# voice_board_kombi_w_gp.net
KiCad netlist of a schematic drawn in EAGLE
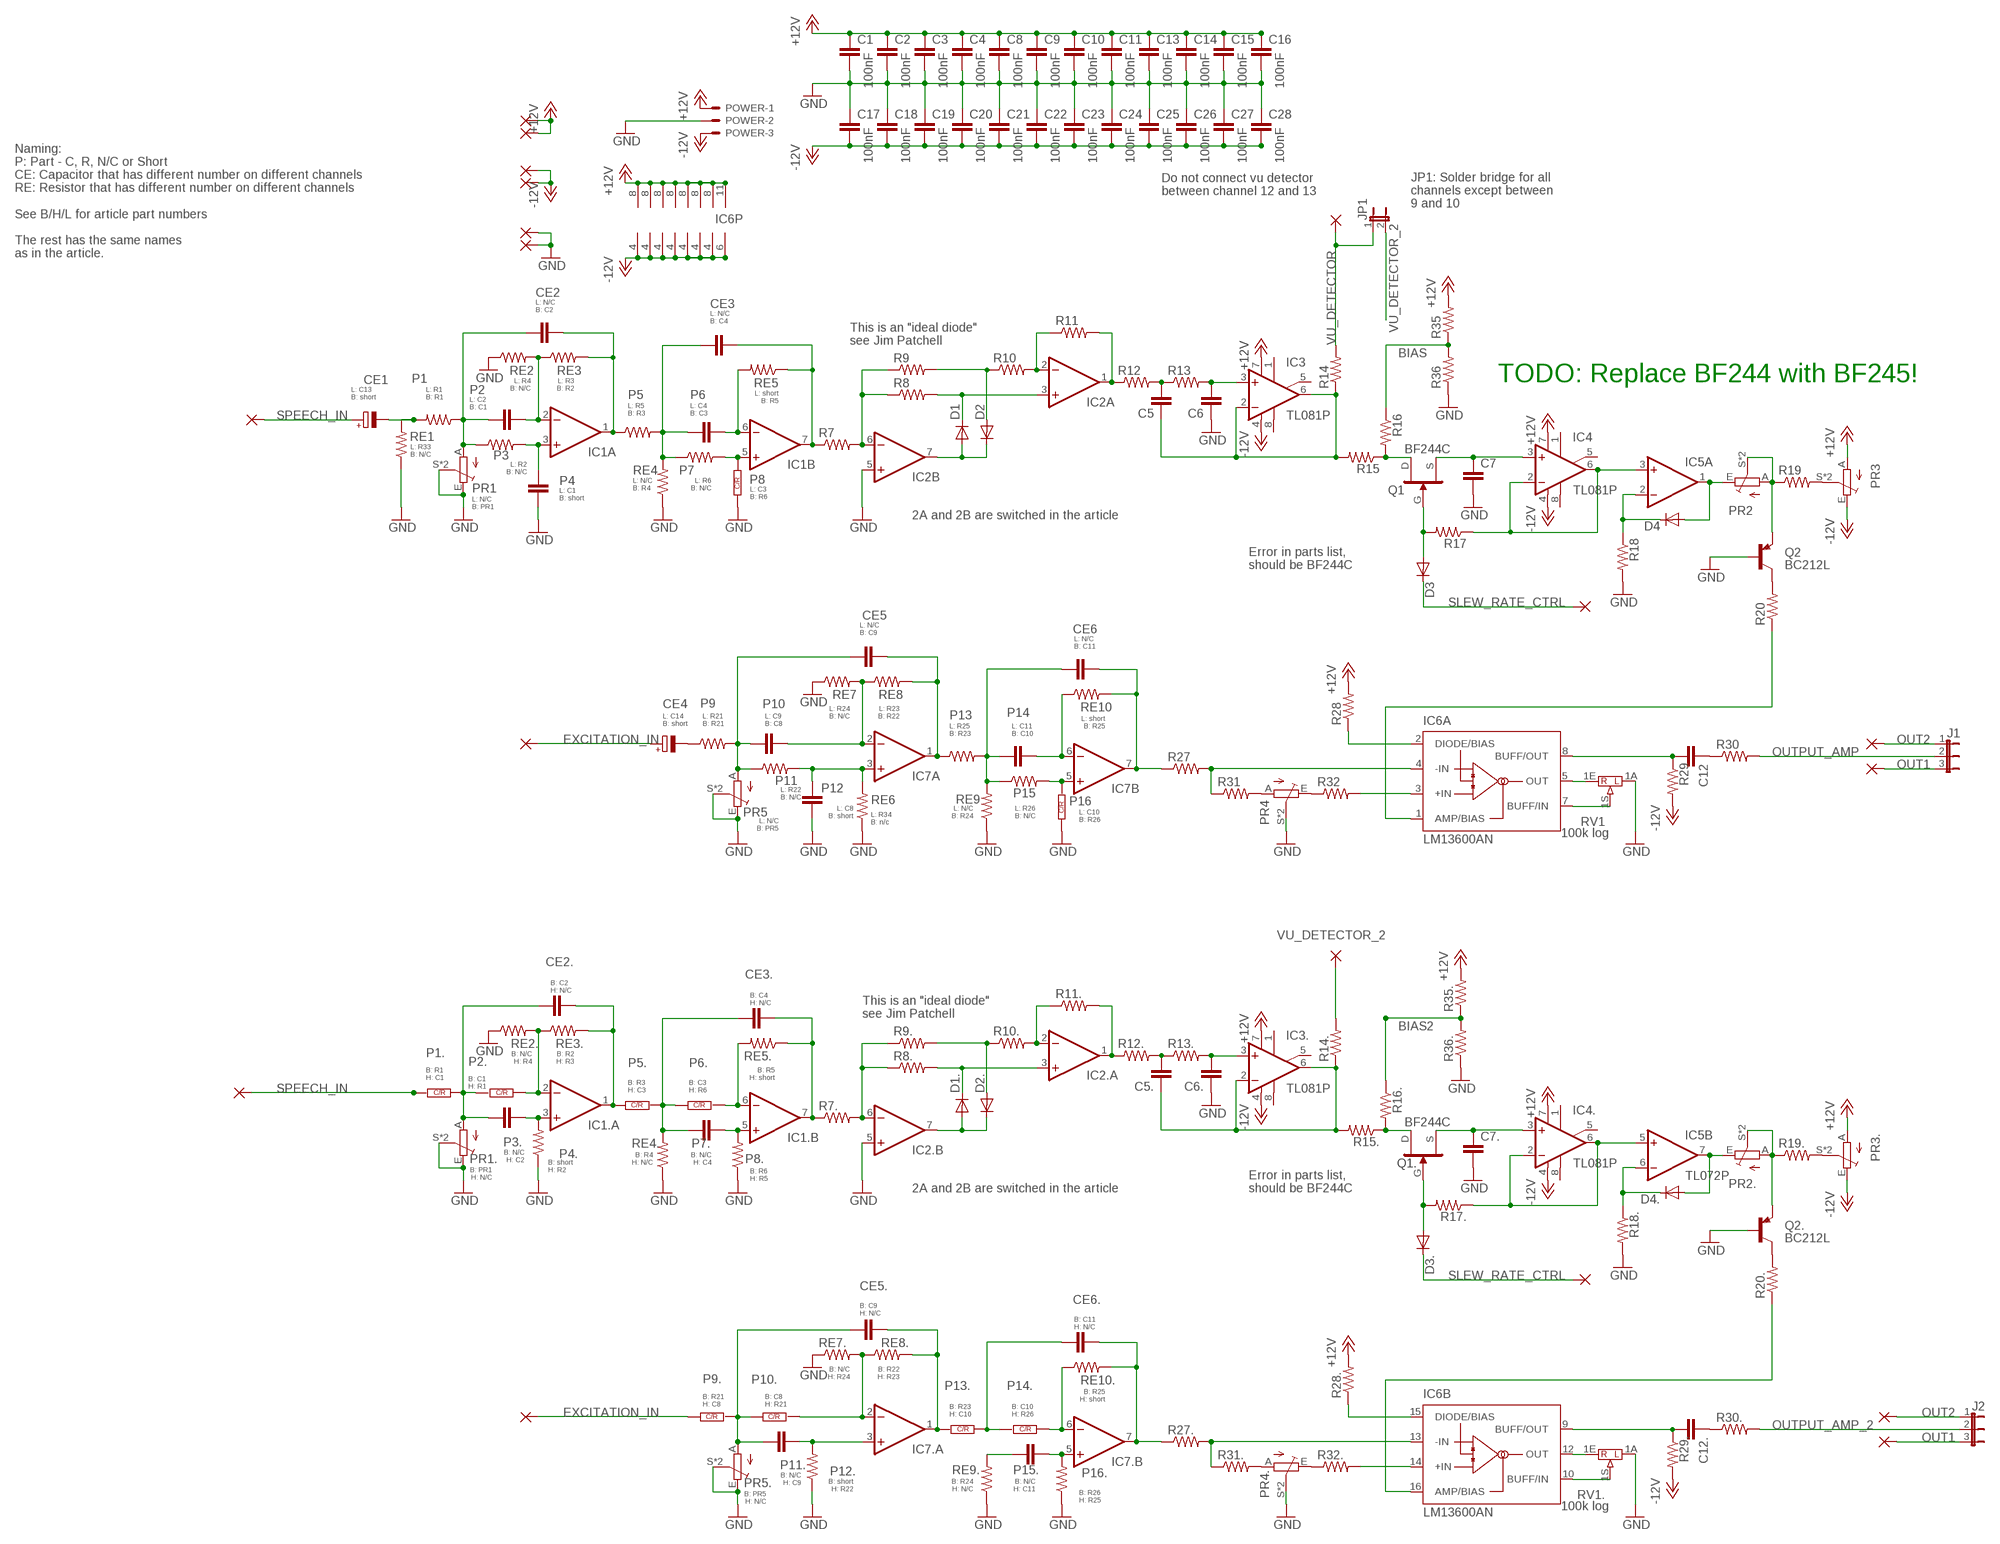
[diagram p0: schematic, sheet 1]

(export (version "E")
  (design (tool "Eeschema 10.0.6"))
  (components
    (comp (ref "C1")
      (value "100nF")
      (footprint "eagle-import:C0603")
      (libsource (lib "eagle-import") (part "C-EUC0603"))
    )
    (comp (ref "C2")
      (value "100nF")
      (footprint "eagle-import:C0603")
      (libsource (lib "eagle-import") (part "C-EUC0603"))
    )
    (comp (ref "C3")
      (value "100nF")
      (footprint "eagle-import:C0603")
      (libsource (lib "eagle-import") (part "C-EUC0603"))
    )
    (comp (ref "C4")
      (value "100nF")
      (footprint "eagle-import:C0603")
      (libsource (lib "eagle-import") (part "C-EUC0603"))
    )
    (comp (ref "C5")
      (value "C-EU050-035X075")
      (footprint "eagle-import:C050-035X075")
      (libsource (lib "eagle-import") (part "C-EU050-035X075"))
    )
    (comp (ref "C5.")
      (value "C-EU050-035X075")
      (footprint "eagle-import:C050-035X075")
      (libsource (lib "eagle-import") (part "C-EU050-035X075"))
    )
    (comp (ref "C6")
      (value "C-EU050-035X075")
      (footprint "eagle-import:C050-035X075")
      (libsource (lib "eagle-import") (part "C-EU050-035X075"))
    )
    (comp (ref "C6.")
      (value "C-EU050-035X075")
      (footprint "eagle-import:C050-035X075")
      (libsource (lib "eagle-import") (part "C-EU050-035X075"))
    )
    (comp (ref "C7")
      (value "C-EU050-035X075")
      (footprint "eagle-import:C050-035X075")
      (libsource (lib "eagle-import") (part "C-EU050-035X075"))
    )
    (comp (ref "C7.")
      (value "C-EU050-035X075")
      (footprint "eagle-import:C050-035X075")
      (libsource (lib "eagle-import") (part "C-EU050-035X075"))
    )
    (comp (ref "C8")
      (value "100nF")
      (footprint "eagle-import:C0603")
      (libsource (lib "eagle-import") (part "C-EUC0603"))
    )
    (comp (ref "C9")
      (value "100nF")
      (footprint "eagle-import:C0603")
      (libsource (lib "eagle-import") (part "C-EUC0603"))
    )
    (comp (ref "C10")
      (value "100nF")
      (footprint "eagle-import:C0603")
      (libsource (lib "eagle-import") (part "C-EUC0603"))
    )
    (comp (ref "C11")
      (value "100nF")
      (footprint "eagle-import:C0603")
      (libsource (lib "eagle-import") (part "C-EUC0603"))
    )
    (comp (ref "C12")
      (value "C-EU050-035X075")
      (footprint "eagle-import:C050-035X075")
      (libsource (lib "eagle-import") (part "C-EU050-035X075"))
    )
    (comp (ref "C12.")
      (value "C-EU050-035X075")
      (footprint "eagle-import:C050-035X075")
      (libsource (lib "eagle-import") (part "C-EU050-035X075"))
    )
    (comp (ref "C13")
      (value "100nF")
      (footprint "eagle-import:C0603")
      (libsource (lib "eagle-import") (part "C-EUC0603"))
    )
    (comp (ref "C14")
      (value "100nF")
      (footprint "eagle-import:C0603")
      (libsource (lib "eagle-import") (part "C-EUC0603"))
    )
    (comp (ref "C15")
      (value "100nF")
      (footprint "eagle-import:C0603")
      (libsource (lib "eagle-import") (part "C-EUC0603"))
    )
    (comp (ref "C16")
      (value "100nF")
      (footprint "eagle-import:C0603")
      (libsource (lib "eagle-import") (part "C-EUC0603"))
    )
    (comp (ref "C17")
      (value "100nF")
      (footprint "eagle-import:C0603")
      (libsource (lib "eagle-import") (part "C-EUC0603"))
    )
    (comp (ref "C18")
      (value "100nF")
      (footprint "eagle-import:C0603")
      (libsource (lib "eagle-import") (part "C-EUC0603"))
    )
    (comp (ref "C19")
      (value "100nF")
      (footprint "eagle-import:C0603")
      (libsource (lib "eagle-import") (part "C-EUC0603"))
    )
    (comp (ref "C20")
      (value "100nF")
      (footprint "eagle-import:C0603")
      (libsource (lib "eagle-import") (part "C-EUC0603"))
    )
    (comp (ref "C21")
      (value "100nF")
      (footprint "eagle-import:C0603")
      (libsource (lib "eagle-import") (part "C-EUC0603"))
    )
    (comp (ref "C22")
      (value "100nF")
      (footprint "eagle-import:C0603")
      (libsource (lib "eagle-import") (part "C-EUC0603"))
    )
    (comp (ref "C23")
      (value "100nF")
      (footprint "eagle-import:C0603")
      (libsource (lib "eagle-import") (part "C-EUC0603"))
    )
    (comp (ref "C24")
      (value "100nF")
      (footprint "eagle-import:C0603")
      (libsource (lib "eagle-import") (part "C-EUC0603"))
    )
    (comp (ref "C25")
      (value "100nF")
      (footprint "eagle-import:C0603")
      (libsource (lib "eagle-import") (part "C-EUC0603"))
    )
    (comp (ref "C26")
      (value "100nF")
      (footprint "eagle-import:C0603")
      (libsource (lib "eagle-import") (part "C-EUC0603"))
    )
    (comp (ref "C27")
      (value "100nF")
      (footprint "eagle-import:C0603")
      (libsource (lib "eagle-import") (part "C-EUC0603"))
    )
    (comp (ref "C28")
      (value "100nF")
      (footprint "eagle-import:C0603")
      (libsource (lib "eagle-import") (part "C-EUC0603"))
    )
    (comp (ref "CE1")
      (value "CPOL-EUE2-4")
      (footprint "eagle-import:E2-4")
      (libsource (lib "eagle-import") (part "CPOL-EUE2-4"))
    )
    (comp (ref "CE2")
      (value "C-EU050-035X075")
      (footprint "eagle-import:C050-035X075")
      (libsource (lib "eagle-import") (part "C-EU050-035X075"))
    )
    (comp (ref "CE2.")
      (value "C-EU050-035X075")
      (footprint "eagle-import:C050-035X075")
      (libsource (lib "eagle-import") (part "C-EU050-035X075"))
    )
    (comp (ref "CE3")
      (value "C-EU050-035X075")
      (footprint "eagle-import:C050-035X075")
      (libsource (lib "eagle-import") (part "C-EU050-035X075"))
    )
    (comp (ref "CE3.")
      (value "C-EU050-035X075")
      (footprint "eagle-import:C050-035X075")
      (libsource (lib "eagle-import") (part "C-EU050-035X075"))
    )
    (comp (ref "CE4")
      (value "CPOL-EUE2-4")
      (footprint "eagle-import:E2-4")
      (libsource (lib "eagle-import") (part "CPOL-EUE2-4"))
    )
    (comp (ref "CE5")
      (value "C-EU050-035X075")
      (footprint "eagle-import:C050-035X075")
      (libsource (lib "eagle-import") (part "C-EU050-035X075"))
    )
    (comp (ref "CE5.")
      (value "C-EU050-035X075")
      (footprint "eagle-import:C050-035X075")
      (libsource (lib "eagle-import") (part "C-EU050-035X075"))
    )
    (comp (ref "CE6")
      (value "C-EU050-035X075")
      (footprint "eagle-import:C050-035X075")
      (libsource (lib "eagle-import") (part "C-EU050-035X075"))
    )
    (comp (ref "CE6.")
      (value "C-EU050-035X075")
      (footprint "eagle-import:C050-035X075")
      (libsource (lib "eagle-import") (part "C-EU050-035X075"))
    )
    (comp (ref "D1")
      (value "DIODE-D-5")
      (footprint "eagle-import:D-5")
      (libsource (lib "eagle-import") (part "DIODE-D-5"))
    )
    (comp (ref "D1.")
      (value "DIODE-D-5")
      (footprint "eagle-import:D-5")
      (libsource (lib "eagle-import") (part "DIODE-D-5"))
    )
    (comp (ref "D2")
      (value "DIODE-D-5")
      (footprint "eagle-import:D-5")
      (libsource (lib "eagle-import") (part "DIODE-D-5"))
    )
    (comp (ref "D2.")
      (value "DIODE-D-5")
      (footprint "eagle-import:D-5")
      (libsource (lib "eagle-import") (part "DIODE-D-5"))
    )
    (comp (ref "D3")
      (value "DIODE-D-5")
      (footprint "eagle-import:D-5")
      (libsource (lib "eagle-import") (part "DIODE-D-5"))
    )
    (comp (ref "D3.")
      (value "DIODE-D-5")
      (footprint "eagle-import:D-5")
      (libsource (lib "eagle-import") (part "DIODE-D-5"))
    )
    (comp (ref "D4")
      (value "DIODE-D-5")
      (footprint "eagle-import:D-5")
      (libsource (lib "eagle-import") (part "DIODE-D-5"))
    )
    (comp (ref "D4.")
      (value "DIODE-D-5")
      (footprint "eagle-import:D-5")
      (libsource (lib "eagle-import") (part "DIODE-D-5"))
    )
    (comp (ref "IC1")
      (value "TL072P")
      (footprint "eagle-import:DIL08")
      (libsource (lib "eagle-import") (part "TL072P"))
    )
    (comp (ref "IC1.")
      (value "TL072P")
      (footprint "eagle-import:DIL08")
      (libsource (lib "eagle-import") (part "TL072P"))
    )
    (comp (ref "IC2")
      (value "TL072P")
      (footprint "eagle-import:DIL08")
      (libsource (lib "eagle-import") (part "TL072P"))
    )
    (comp (ref "IC2.")
      (value "TL072P")
      (footprint "eagle-import:DIL08")
      (libsource (lib "eagle-import") (part "TL072P"))
    )
    (comp (ref "IC3")
      (value "TL081P")
      (footprint "eagle-import:DIL08")
      (libsource (lib "eagle-import") (part "TL081P"))
    )
    (comp (ref "IC3.")
      (value "TL081P")
      (footprint "eagle-import:DIL08")
      (libsource (lib "eagle-import") (part "TL081P"))
    )
    (comp (ref "IC4")
      (value "TL081P")
      (footprint "eagle-import:DIL08")
      (libsource (lib "eagle-import") (part "TL081P"))
    )
    (comp (ref "IC4.")
      (value "TL081P")
      (footprint "eagle-import:DIL08")
      (libsource (lib "eagle-import") (part "TL081P"))
    )
    (comp (ref "IC5")
      (value "TL072P")
      (footprint "eagle-import:DIL08")
      (libsource (lib "eagle-import") (part "TL072P"))
    )
    (comp (ref "IC6")
      (value "LM13600AN")
      (footprint "eagle-import:DIL16")
      (libsource (lib "eagle-import") (part "LM13600NA"))
    )
    (comp (ref "IC7")
      (value "TL072P")
      (footprint "eagle-import:DIL08")
      (libsource (lib "eagle-import") (part "TL072P"))
    )
    (comp (ref "IC7.")
      (value "TL072P")
      (footprint "eagle-import:DIL08")
      (libsource (lib "eagle-import") (part "TL072P"))
    )
    (comp (ref "J1")
      (value "JP2E")
      (footprint "eagle-import:JP2")
      (libsource (lib "eagle-import") (part "JP2E"))
    )
    (comp (ref "J2")
      (value "JP2E")
      (footprint "eagle-import:JP2")
      (libsource (lib "eagle-import") (part "JP2E"))
    )
    (comp (ref "JP1")
      (value "JP1E")
      (footprint "eagle-import:JP1")
      (libsource (lib "eagle-import") (part "JP1E"))
    )
    (comp (ref "P1")
      (value "R-US_0207/7")
      (footprint "eagle-import:0207_7")
      (libsource (lib "eagle-import") (part "R-US_0207/7"))
    )
    (comp (ref "P1.")
      (value "C-OR-R050_075-035X100")
      (footprint "eagle-import:P050_075-035X100J")
      (libsource (lib "eagle-import") (part "C-OR-R050_075-035X100"))
    )
    (comp (ref "P2")
      (value "C-EU050-035X075")
      (footprint "eagle-import:C050-035X075")
      (libsource (lib "eagle-import") (part "C-EU050-035X075"))
    )
    (comp (ref "P2.")
      (value "C-OR-R050_075-035X100")
      (footprint "eagle-import:P050_075-035X100J")
      (libsource (lib "eagle-import") (part "C-OR-R050_075-035X100"))
    )
    (comp (ref "P3")
      (value "R-US_0207/7")
      (footprint "eagle-import:0207_7")
      (libsource (lib "eagle-import") (part "R-US_0207/7"))
    )
    (comp (ref "P3.")
      (value "C-EU050-035X075")
      (footprint "eagle-import:C050-035X075")
      (libsource (lib "eagle-import") (part "C-EU050-035X075"))
    )
    (comp (ref "P4")
      (value "C-EU050-035X075")
      (footprint "eagle-import:C050-035X075")
      (libsource (lib "eagle-import") (part "C-EU050-035X075"))
    )
    (comp (ref "P4.")
      (value "R-US_0207/7")
      (footprint "eagle-import:0207_7")
      (libsource (lib "eagle-import") (part "R-US_0207/7"))
    )
    (comp (ref "P5")
      (value "R-US_0207/7")
      (footprint "eagle-import:0207_7")
      (libsource (lib "eagle-import") (part "R-US_0207/7"))
    )
    (comp (ref "P5.")
      (value "C-OR-R050_075-035X100")
      (footprint "eagle-import:P050_075-035X100J")
      (libsource (lib "eagle-import") (part "C-OR-R050_075-035X100"))
    )
    (comp (ref "P6")
      (value "C-EU050-035X075")
      (footprint "eagle-import:C050-035X075")
      (libsource (lib "eagle-import") (part "C-EU050-035X075"))
    )
    (comp (ref "P6.")
      (value "C-OR-R050_075-035X100")
      (footprint "eagle-import:P050_075-035X100J")
      (libsource (lib "eagle-import") (part "C-OR-R050_075-035X100"))
    )
    (comp (ref "P7")
      (value "R-US_0207/7")
      (footprint "eagle-import:0207_7")
      (libsource (lib "eagle-import") (part "R-US_0207/7"))
    )
    (comp (ref "P7.")
      (value "C-EU050-035X075")
      (footprint "eagle-import:C050-035X075")
      (libsource (lib "eagle-import") (part "C-EU050-035X075"))
    )
    (comp (ref "P8")
      (value "C-OR-R050_075-035X100")
      (footprint "eagle-import:P050_075-035X100J")
      (libsource (lib "eagle-import") (part "C-OR-R050_075-035X100"))
    )
    (comp (ref "P8.")
      (value "R-US_0207/7")
      (footprint "eagle-import:0207_7")
      (libsource (lib "eagle-import") (part "R-US_0207/7"))
    )
    (comp (ref "P9")
      (value "R-US_0207/7")
      (footprint "eagle-import:0207_7")
      (libsource (lib "eagle-import") (part "R-US_0207/7"))
    )
    (comp (ref "P9.")
      (value "C-OR-R050_075-035X100")
      (footprint "eagle-import:P050_075-035X100J")
      (libsource (lib "eagle-import") (part "C-OR-R050_075-035X100"))
    )
    (comp (ref "P10")
      (value "C-EU050-035X075")
      (footprint "eagle-import:C050-035X075")
      (libsource (lib "eagle-import") (part "C-EU050-035X075"))
    )
    (comp (ref "P10.")
      (value "C-OR-R050_075-035X100")
      (footprint "eagle-import:P050_075-035X100J")
      (libsource (lib "eagle-import") (part "C-OR-R050_075-035X100"))
    )
    (comp (ref "P11")
      (value "R-US_0207/7")
      (footprint "eagle-import:0207_7")
      (libsource (lib "eagle-import") (part "R-US_0207/7"))
    )
    (comp (ref "P11.")
      (value "C-EU050-035X075")
      (footprint "eagle-import:C050-035X075")
      (libsource (lib "eagle-import") (part "C-EU050-035X075"))
    )
    (comp (ref "P12")
      (value "C-EU050-035X075")
      (footprint "eagle-import:C050-035X075")
      (libsource (lib "eagle-import") (part "C-EU050-035X075"))
    )
    (comp (ref "P12.")
      (value "R-US_0207/7")
      (footprint "eagle-import:0207_7")
      (libsource (lib "eagle-import") (part "R-US_0207/7"))
    )
    (comp (ref "P13")
      (value "R-US_0207/7")
      (footprint "eagle-import:0207_7")
      (libsource (lib "eagle-import") (part "R-US_0207/7"))
    )
    (comp (ref "P13.")
      (value "C-OR-R050_075-035X100")
      (footprint "eagle-import:P050_075-035X100J")
      (libsource (lib "eagle-import") (part "C-OR-R050_075-035X100"))
    )
    (comp (ref "P14")
      (value "C-EU050-035X075")
      (footprint "eagle-import:C050-035X075")
      (libsource (lib "eagle-import") (part "C-EU050-035X075"))
    )
    (comp (ref "P14.")
      (value "C-OR-R050_075-035X100")
      (footprint "eagle-import:P050_075-035X100J")
      (libsource (lib "eagle-import") (part "C-OR-R050_075-035X100"))
    )
    (comp (ref "P15")
      (value "R-US_0207/7")
      (footprint "eagle-import:0207_7")
      (libsource (lib "eagle-import") (part "R-US_0207/7"))
    )
    (comp (ref "P15.")
      (value "C-EU050-035X075")
      (footprint "eagle-import:C050-035X075")
      (libsource (lib "eagle-import") (part "C-EU050-035X075"))
    )
    (comp (ref "P16")
      (value "C-OR-R050_075-035X100")
      (footprint "eagle-import:P050_075-035X100J")
      (libsource (lib "eagle-import") (part "C-OR-R050_075-035X100"))
    )
    (comp (ref "P16.")
      (value "R-US_0207/7")
      (footprint "eagle-import:0207_7")
      (libsource (lib "eagle-import") (part "R-US_0207/7"))
    )
    (comp (ref "PAD1")
      (value "WIREPAD2,54/1,1")
      (footprint "eagle-import:2,54_1,1")
      (libsource (lib "eagle-import") (part "WIREPAD2,54/1,1"))
    )
    (comp (ref "PAD2")
      (value "WIREPAD2,54/1,1")
      (footprint "eagle-import:2,54_1,1")
      (libsource (lib "eagle-import") (part "WIREPAD2,54/1,1"))
    )
    (comp (ref "PAD3")
      (value "WIREPAD2,54/1,1")
      (footprint "eagle-import:2,54_1,1")
      (libsource (lib "eagle-import") (part "WIREPAD2,54/1,1"))
    )
    (comp (ref "PAD4")
      (value "WIREPAD2,54/1,1")
      (footprint "eagle-import:2,54_1,1")
      (libsource (lib "eagle-import") (part "WIREPAD2,54/1,1"))
    )
    (comp (ref "PAD5")
      (value "WIREPAD2,54/1,1")
      (footprint "eagle-import:2,54_1,1")
      (libsource (lib "eagle-import") (part "WIREPAD2,54/1,1"))
    )
    (comp (ref "PAD6")
      (value "WIREPAD2,54/1,1")
      (footprint "eagle-import:2,54_1,1")
      (libsource (lib "eagle-import") (part "WIREPAD2,54/1,1"))
    )
    (comp (ref "PAD7")
      (value "WIREPAD2,54/1,1")
      (footprint "eagle-import:2,54_1,1")
      (libsource (lib "eagle-import") (part "WIREPAD2,54/1,1"))
    )
    (comp (ref "PAD8")
      (value "WIREPAD2,54/1,1")
      (footprint "eagle-import:2,54_1,1")
      (libsource (lib "eagle-import") (part "WIREPAD2,54/1,1"))
    )
    (comp (ref "PAD9")
      (value "WIREPAD2,54/1,1")
      (footprint "eagle-import:2,54_1,1")
      (libsource (lib "eagle-import") (part "WIREPAD2,54/1,1"))
    )
    (comp (ref "PAD10")
      (value "WIREPAD2,54/1,1")
      (footprint "eagle-import:2,54_1,1")
      (libsource (lib "eagle-import") (part "WIREPAD2,54/1,1"))
    )
    (comp (ref "PAD11")
      (value "WIREPAD2,54/1,1")
      (footprint "eagle-import:2,54_1,1")
      (libsource (lib "eagle-import") (part "WIREPAD2,54/1,1"))
    )
    (comp (ref "PAD12")
      (value "WIREPAD2,54/1,1")
      (footprint "eagle-import:2,54_1,1")
      (libsource (lib "eagle-import") (part "WIREPAD2,54/1,1"))
    )
    (comp (ref "PAD13")
      (value "WIREPAD2,54/1,1")
      (footprint "eagle-import:2,54_1,1")
      (libsource (lib "eagle-import") (part "WIREPAD2,54/1,1"))
    )
    (comp (ref "PAD14")
      (value "WIREPAD2,54/1,1")
      (footprint "eagle-import:2,54_1,1")
      (libsource (lib "eagle-import") (part "WIREPAD2,54/1,1"))
    )
    (comp (ref "PAD15")
      (value "WIREPAD2,54/1,1")
      (footprint "eagle-import:2,54_1,1")
      (libsource (lib "eagle-import") (part "WIREPAD2,54/1,1"))
    )
    (comp (ref "PAD16")
      (value "WIREPAD2,54/1,1")
      (footprint "eagle-import:2,54_1,1")
      (libsource (lib "eagle-import") (part "WIREPAD2,54/1,1"))
    )
    (comp (ref "PAD17")
      (value "WIREPAD2,54/1,1")
      (footprint "eagle-import:2,54_1,1")
      (libsource (lib "eagle-import") (part "WIREPAD2,54/1,1"))
    )
    (comp (ref "PAD18")
      (value "WIREPAD2,54/1,1")
      (footprint "eagle-import:2,54_1,1")
      (libsource (lib "eagle-import") (part "WIREPAD2,54/1,1"))
    )
    (comp (ref "POWER")
      (value "KK-156-3")
      (footprint "eagle-import:KK-156-3")
      (libsource (lib "eagle-import") (part "KK-156-3"))
    )
    (comp (ref "PR1")
      (value "TRIM_EU-PT10-R065")
      (footprint "eagle-import:MULTIPOT_2_J")
      (libsource (lib "eagle-import") (part "TRIM_EU-PT10-R065"))
    )
    (comp (ref "PR1.")
      (value "TRIM_EU-PT10-R065")
      (footprint "eagle-import:MULTIPOT_2_J")
      (libsource (lib "eagle-import") (part "TRIM_EU-PT10-R065"))
    )
    (comp (ref "PR2")
      (value "TRIM_EU-PT10-R065")
      (footprint "eagle-import:MULTIPOT_2_J")
      (libsource (lib "eagle-import") (part "TRIM_EU-PT10-R065"))
    )
    (comp (ref "PR2.")
      (value "TRIM_EU-PT10-R065")
      (footprint "eagle-import:MULTIPOT_2_J")
      (libsource (lib "eagle-import") (part "TRIM_EU-PT10-R065"))
    )
    (comp (ref "PR3")
      (value "TRIM_EU-PT10-R065")
      (footprint "eagle-import:MULTIPOT_2_J")
      (libsource (lib "eagle-import") (part "TRIM_EU-PT10-R065"))
    )
    (comp (ref "PR3.")
      (value "TRIM_EU-PT10-R065")
      (footprint "eagle-import:MULTIPOT_2_J")
      (libsource (lib "eagle-import") (part "TRIM_EU-PT10-R065"))
    )
    (comp (ref "PR4")
      (value "TRIM_EU-PT10-R065")
      (footprint "eagle-import:MULTIPOT_2_J")
      (libsource (lib "eagle-import") (part "TRIM_EU-PT10-R065"))
    )
    (comp (ref "PR4.")
      (value "TRIM_EU-PT10-R065")
      (footprint "eagle-import:MULTIPOT_2_J")
      (libsource (lib "eagle-import") (part "TRIM_EU-PT10-R065"))
    )
    (comp (ref "PR5")
      (value "TRIM_EU-PT10-R065")
      (footprint "eagle-import:MULTIPOT_2_J")
      (libsource (lib "eagle-import") (part "TRIM_EU-PT10-R065"))
    )
    (comp (ref "PR5.")
      (value "TRIM_EU-PT10-R065")
      (footprint "eagle-import:MULTIPOT_2_J")
      (libsource (lib "eagle-import") (part "TRIM_EU-PT10-R065"))
    )
    (comp (ref "Q1")
      (value "BF244C")
      (footprint "eagle-import:TO92-DGSD-J")
      (libsource (lib "eagle-import") (part "N-CHANNEL-JFET-JIL-DGSD"))
    )
    (comp (ref "Q1.")
      (value "BF244C")
      (footprint "eagle-import:TO92-DGSD-J")
      (libsource (lib "eagle-import") (part "N-CHANNEL-JFET-JIL-DGSD"))
    )
    (comp (ref "Q2")
      (value "BC212L")
      (footprint "eagle-import:TO92-ECB")
      (libsource (lib "eagle-import") (part "-PNP-TO92-ECB"))
    )
    (comp (ref "Q2.")
      (value "BC212L")
      (footprint "eagle-import:TO92-ECB")
      (libsource (lib "eagle-import") (part "-PNP-TO92-ECB"))
    )
    (comp (ref "R7")
      (value "R-US_0207/7")
      (footprint "eagle-import:0207_7")
      (libsource (lib "eagle-import") (part "R-US_0207/7"))
    )
    (comp (ref "R7.")
      (value "R-US_0207/7")
      (footprint "eagle-import:0207_7")
      (libsource (lib "eagle-import") (part "R-US_0207/7"))
    )
    (comp (ref "R8")
      (value "R-US_0207/7")
      (footprint "eagle-import:0207_7")
      (libsource (lib "eagle-import") (part "R-US_0207/7"))
    )
    (comp (ref "R8.")
      (value "R-US_0207/7")
      (footprint "eagle-import:0207_7")
      (libsource (lib "eagle-import") (part "R-US_0207/7"))
    )
    (comp (ref "R9")
      (value "R-US_0207/7")
      (footprint "eagle-import:0207_7")
      (libsource (lib "eagle-import") (part "R-US_0207/7"))
    )
    (comp (ref "R9.")
      (value "R-US_0207/7")
      (footprint "eagle-import:0207_7")
      (libsource (lib "eagle-import") (part "R-US_0207/7"))
    )
    (comp (ref "R10")
      (value "R-US_0207/7")
      (footprint "eagle-import:0207_7")
      (libsource (lib "eagle-import") (part "R-US_0207/7"))
    )
    (comp (ref "R10.")
      (value "R-US_0207/7")
      (footprint "eagle-import:0207_7")
      (libsource (lib "eagle-import") (part "R-US_0207/7"))
    )
    (comp (ref "R11")
      (value "R-US_0207/7")
      (footprint "eagle-import:0207_7")
      (libsource (lib "eagle-import") (part "R-US_0207/7"))
    )
    (comp (ref "R11.")
      (value "R-US_0207/7")
      (footprint "eagle-import:0207_7")
      (libsource (lib "eagle-import") (part "R-US_0207/7"))
    )
    (comp (ref "R12")
      (value "R-US_0207/7")
      (footprint "eagle-import:0207_7")
      (libsource (lib "eagle-import") (part "R-US_0207/7"))
    )
    (comp (ref "R12.")
      (value "R-US_0207/7")
      (footprint "eagle-import:0207_7")
      (libsource (lib "eagle-import") (part "R-US_0207/7"))
    )
    (comp (ref "R13")
      (value "R-US_0207/7")
      (footprint "eagle-import:0207_7")
      (libsource (lib "eagle-import") (part "R-US_0207/7"))
    )
    (comp (ref "R13.")
      (value "R-US_0207/7")
      (footprint "eagle-import:0207_7")
      (libsource (lib "eagle-import") (part "R-US_0207/7"))
    )
    (comp (ref "R14")
      (value "R-US_0207/7")
      (footprint "eagle-import:0207_7")
      (libsource (lib "eagle-import") (part "R-US_0207/7"))
    )
    (comp (ref "R14.")
      (value "R-US_0207/7")
      (footprint "eagle-import:0207_7")
      (libsource (lib "eagle-import") (part "R-US_0207/7"))
    )
    (comp (ref "R15")
      (value "R-US_0207/7")
      (footprint "eagle-import:0207_7")
      (libsource (lib "eagle-import") (part "R-US_0207/7"))
    )
    (comp (ref "R15.")
      (value "R-US_0207/7")
      (footprint "eagle-import:0207_7")
      (libsource (lib "eagle-import") (part "R-US_0207/7"))
    )
    (comp (ref "R16")
      (value "R-US_0207/7")
      (footprint "eagle-import:0207_7")
      (libsource (lib "eagle-import") (part "R-US_0207/7"))
    )
    (comp (ref "R16.")
      (value "R-US_0207/7")
      (footprint "eagle-import:0207_7")
      (libsource (lib "eagle-import") (part "R-US_0207/7"))
    )
    (comp (ref "R17")
      (value "R-US_0207/7")
      (footprint "eagle-import:0207_7")
      (libsource (lib "eagle-import") (part "R-US_0207/7"))
    )
    (comp (ref "R17.")
      (value "R-US_0207/7")
      (footprint "eagle-import:0207_7")
      (libsource (lib "eagle-import") (part "R-US_0207/7"))
    )
    (comp (ref "R18")
      (value "R-US_0207/7")
      (footprint "eagle-import:0207_7")
      (libsource (lib "eagle-import") (part "R-US_0207/7"))
    )
    (comp (ref "R18.")
      (value "R-US_0207/7")
      (footprint "eagle-import:0207_7")
      (libsource (lib "eagle-import") (part "R-US_0207/7"))
    )
    (comp (ref "R19")
      (value "R-US_0207/7")
      (footprint "eagle-import:0207_7")
      (libsource (lib "eagle-import") (part "R-US_0207/7"))
    )
    (comp (ref "R19.")
      (value "R-US_0207/7")
      (footprint "eagle-import:0207_7")
      (libsource (lib "eagle-import") (part "R-US_0207/7"))
    )
    (comp (ref "R20")
      (value "R-US_0207/7")
      (footprint "eagle-import:0207_7")
      (libsource (lib "eagle-import") (part "R-US_0207/7"))
    )
    (comp (ref "R20.")
      (value "R-US_0207/7")
      (footprint "eagle-import:0207_7")
      (libsource (lib "eagle-import") (part "R-US_0207/7"))
    )
    (comp (ref "R27")
      (value "R-US_0207/7")
      (footprint "eagle-import:0207_7")
      (libsource (lib "eagle-import") (part "R-US_0207/7"))
    )
    (comp (ref "R27.")
      (value "R-US_0207/7")
      (footprint "eagle-import:0207_7")
      (libsource (lib "eagle-import") (part "R-US_0207/7"))
    )
    (comp (ref "R28")
      (value "R-US_0207/7")
      (footprint "eagle-import:0207_7")
      (libsource (lib "eagle-import") (part "R-US_0207/7"))
    )
    (comp (ref "R28.")
      (value "R-US_0207/7")
      (footprint "eagle-import:0207_7")
      (libsource (lib "eagle-import") (part "R-US_0207/7"))
    )
    (comp (ref "R29")
      (value "R-US_0207/7")
      (footprint "eagle-import:0207_7")
      (libsource (lib "eagle-import") (part "R-US_0207/7"))
    )
    (comp (ref "R29.")
      (value "R-US_0207/7")
      (footprint "eagle-import:0207_7")
      (libsource (lib "eagle-import") (part "R-US_0207/7"))
    )
    (comp (ref "R30")
      (value "R-US_0207/7")
      (footprint "eagle-import:0207_7")
      (libsource (lib "eagle-import") (part "R-US_0207/7"))
    )
    (comp (ref "R30.")
      (value "R-US_0207/7")
      (footprint "eagle-import:0207_7")
      (libsource (lib "eagle-import") (part "R-US_0207/7"))
    )
    (comp (ref "R31")
      (value "R-US_0207/7")
      (footprint "eagle-import:0207_7")
      (libsource (lib "eagle-import") (part "R-US_0207/7"))
    )
    (comp (ref "R31.")
      (value "R-US_0207/7")
      (footprint "eagle-import:0207_7")
      (libsource (lib "eagle-import") (part "R-US_0207/7"))
    )
    (comp (ref "R32")
      (value "R-US_0207/7")
      (footprint "eagle-import:0207_7")
      (libsource (lib "eagle-import") (part "R-US_0207/7"))
    )
    (comp (ref "R32.")
      (value "R-US_0207/7")
      (footprint "eagle-import:0207_7")
      (libsource (lib "eagle-import") (part "R-US_0207/7"))
    )
    (comp (ref "R35")
      (value "R-US_0207/7")
      (footprint "eagle-import:0207_7")
      (libsource (lib "eagle-import") (part "R-US_0207/7"))
    )
    (comp (ref "R35.")
      (value "R-US_0207/7")
      (footprint "eagle-import:0207_7")
      (libsource (lib "eagle-import") (part "R-US_0207/7"))
    )
    (comp (ref "R36")
      (value "R-US_0207/7")
      (footprint "eagle-import:0207_7")
      (libsource (lib "eagle-import") (part "R-US_0207/7"))
    )
    (comp (ref "R36.")
      (value "R-US_0207/7")
      (footprint "eagle-import:0207_7")
      (libsource (lib "eagle-import") (part "R-US_0207/7"))
    )
    (comp (ref "RE1")
      (value "R-US_0207/7")
      (footprint "eagle-import:0207_7")
      (libsource (lib "eagle-import") (part "R-US_0207/7"))
    )
    (comp (ref "RE2")
      (value "R-US_0207/7")
      (footprint "eagle-import:0207_7")
      (libsource (lib "eagle-import") (part "R-US_0207/7"))
    )
    (comp (ref "RE2.")
      (value "R-US_0207/7")
      (footprint "eagle-import:0207_7")
      (libsource (lib "eagle-import") (part "R-US_0207/7"))
    )
    (comp (ref "RE3")
      (value "R-US_0207/7")
      (footprint "eagle-import:0207_7")
      (libsource (lib "eagle-import") (part "R-US_0207/7"))
    )
    (comp (ref "RE3.")
      (value "R-US_0207/7")
      (footprint "eagle-import:0207_7")
      (libsource (lib "eagle-import") (part "R-US_0207/7"))
    )
    (comp (ref "RE4")
      (value "R-US_0207/7")
      (footprint "eagle-import:0207_7")
      (libsource (lib "eagle-import") (part "R-US_0207/7"))
    )
    (comp (ref "RE4.")
      (value "R-US_0207/7")
      (footprint "eagle-import:0207_7")
      (libsource (lib "eagle-import") (part "R-US_0207/7"))
    )
    (comp (ref "RE5")
      (value "R-US_0207/7")
      (footprint "eagle-import:0207_7")
      (libsource (lib "eagle-import") (part "R-US_0207/7"))
    )
    (comp (ref "RE5.")
      (value "R-US_0207/7")
      (footprint "eagle-import:0207_7")
      (libsource (lib "eagle-import") (part "R-US_0207/7"))
    )
    (comp (ref "RE6")
      (value "R-US_0204/7")
      (footprint "eagle-import:0204_7")
      (libsource (lib "eagle-import") (part "R-US_0204/7"))
    )
    (comp (ref "RE7")
      (value "R-US_0207/7")
      (footprint "eagle-import:0207_7")
      (libsource (lib "eagle-import") (part "R-US_0207/7"))
    )
    (comp (ref "RE7.")
      (value "R-US_0207/7")
      (footprint "eagle-import:0207_7")
      (libsource (lib "eagle-import") (part "R-US_0207/7"))
    )
    (comp (ref "RE8")
      (value "R-US_0207/7")
      (footprint "eagle-import:0207_7")
      (libsource (lib "eagle-import") (part "R-US_0207/7"))
    )
    (comp (ref "RE8.")
      (value "R-US_0207/7")
      (footprint "eagle-import:0207_7")
      (libsource (lib "eagle-import") (part "R-US_0207/7"))
    )
    (comp (ref "RE9")
      (value "R-US_0207/7")
      (footprint "eagle-import:0207_7")
      (libsource (lib "eagle-import") (part "R-US_0207/7"))
    )
    (comp (ref "RE9.")
      (value "R-US_0207/7")
      (footprint "eagle-import:0207_7")
      (libsource (lib "eagle-import") (part "R-US_0207/7"))
    )
    (comp (ref "RE10")
      (value "R-US_0207/7")
      (footprint "eagle-import:0207_7")
      (libsource (lib "eagle-import") (part "R-US_0207/7"))
    )
    (comp (ref "RE10.")
      (value "R-US_0207/7")
      (footprint "eagle-import:0207_7")
      (libsource (lib "eagle-import") (part "R-US_0207/7"))
    )
    (comp (ref "RV1")
      (value "100k log")
      (footprint "eagle-import:POT16_W_BRACKET-J")
      (libsource (lib "eagle-import") (part "POT16_W_BRACKET{dblquote}{dblquote}"))
    )
    (comp (ref "RV1.")
      (value "100k log")
      (footprint "eagle-import:POT16_W_BRACKET-J")
      (libsource (lib "eagle-import") (part "POT16_W_BRACKET{dblquote}{dblquote}"))
    )
  )
  (nets
    (net (code "1") (name "+12V") (class "Default")
      (node (ref "C1") (pin "1") (pinfunction "1_1") (pintype "passive"))
      (node (ref "C10") (pin "1") (pinfunction "1_1") (pintype "passive"))
      (node (ref "C11") (pin "1") (pinfunction "1_1") (pintype "passive"))
      (node (ref "C13") (pin "1") (pinfunction "1_1") (pintype "passive"))
      (node (ref "C14") (pin "1") (pinfunction "1_1") (pintype "passive"))
      (node (ref "C15") (pin "1") (pinfunction "1_1") (pintype "passive"))
      (node (ref "C16") (pin "1") (pinfunction "1_1") (pintype "passive"))
      (node (ref "C2") (pin "1") (pinfunction "1_1") (pintype "passive"))
      (node (ref "C3") (pin "1") (pinfunction "1_1") (pintype "passive"))
      (node (ref "C4") (pin "1") (pinfunction "1_1") (pintype "passive"))
      (node (ref "C8") (pin "1") (pinfunction "1_1") (pintype "passive"))
      (node (ref "C9") (pin "1") (pinfunction "1_1") (pintype "passive"))
      (node (ref "IC1") (pin "8") (pinfunction "V+_8") (pintype "power_in"))
      (node (ref "IC1.") (pin "8") (pinfunction "V+_8") (pintype "power_in"))
      (node (ref "IC2") (pin "8") (pinfunction "V+_8") (pintype "power_in"))
      (node (ref "IC2.") (pin "8") (pinfunction "V+_8") (pintype "power_in"))
      (node (ref "IC3") (pin "7") (pinfunction "V+_7") (pintype "power_in"))
      (node (ref "IC3.") (pin "7") (pinfunction "V+_7") (pintype "power_in"))
      (node (ref "IC4") (pin "7") (pinfunction "V+_7") (pintype "power_in"))
      (node (ref "IC4.") (pin "7") (pinfunction "V+_7") (pintype "power_in"))
      (node (ref "IC5") (pin "8") (pinfunction "V+_8") (pintype "power_in"))
      (node (ref "IC6") (pin "11") (pinfunction "V+_11") (pintype "power_in"))
      (node (ref "IC7") (pin "8") (pinfunction "V+_8") (pintype "power_in"))
      (node (ref "IC7.") (pin "8") (pinfunction "V+_8") (pintype "power_in"))
      (node (ref "PAD10") (pin "1") (pinfunction "P_1") (pintype "passive"))
      (node (ref "PAD9") (pin "1") (pinfunction "P_1") (pintype "passive"))
      (node (ref "POWER") (pin "1") (pinfunction "S_1") (pintype "passive"))
      (node (ref "PR3") (pin "A") (pinfunction "A_A") (pintype "passive"))
      (node (ref "PR3.") (pin "A") (pinfunction "A_A") (pintype "passive"))
      (node (ref "R28") (pin "2") (pinfunction "2_2") (pintype "passive"))
      (node (ref "R28.") (pin "2") (pinfunction "2_2") (pintype "passive"))
      (node (ref "R35") (pin "2") (pinfunction "2_2") (pintype "passive"))
      (node (ref "R35.") (pin "2") (pinfunction "2_2") (pintype "passive"))
    )
    (net (code "2") (name "-12V") (class "Default")
      (node (ref "C17") (pin "2") (pinfunction "2_2") (pintype "passive"))
      (node (ref "C18") (pin "2") (pinfunction "2_2") (pintype "passive"))
      (node (ref "C19") (pin "2") (pinfunction "2_2") (pintype "passive"))
      (node (ref "C20") (pin "2") (pinfunction "2_2") (pintype "passive"))
      (node (ref "C21") (pin "2") (pinfunction "2_2") (pintype "passive"))
      (node (ref "C22") (pin "2") (pinfunction "2_2") (pintype "passive"))
      (node (ref "C23") (pin "2") (pinfunction "2_2") (pintype "passive"))
      (node (ref "C24") (pin "2") (pinfunction "2_2") (pintype "passive"))
      (node (ref "C25") (pin "2") (pinfunction "2_2") (pintype "passive"))
      (node (ref "C26") (pin "2") (pinfunction "2_2") (pintype "passive"))
      (node (ref "C27") (pin "2") (pinfunction "2_2") (pintype "passive"))
      (node (ref "C28") (pin "2") (pinfunction "2_2") (pintype "passive"))
      (node (ref "IC1") (pin "4") (pinfunction "V-_4") (pintype "power_in"))
      (node (ref "IC1.") (pin "4") (pinfunction "V-_4") (pintype "power_in"))
      (node (ref "IC2") (pin "4") (pinfunction "V-_4") (pintype "power_in"))
      (node (ref "IC2.") (pin "4") (pinfunction "V-_4") (pintype "power_in"))
      (node (ref "IC3") (pin "4") (pinfunction "V-_4") (pintype "power_in"))
      (node (ref "IC3.") (pin "4") (pinfunction "V-_4") (pintype "power_in"))
      (node (ref "IC4") (pin "4") (pinfunction "V-_4") (pintype "power_in"))
      (node (ref "IC4.") (pin "4") (pinfunction "V-_4") (pintype "power_in"))
      (node (ref "IC5") (pin "4") (pinfunction "V-_4") (pintype "power_in"))
      (node (ref "IC6") (pin "6") (pinfunction "V-_6") (pintype "power_in"))
      (node (ref "IC7") (pin "4") (pinfunction "V-_4") (pintype "power_in"))
      (node (ref "IC7.") (pin "4") (pinfunction "V-_4") (pintype "power_in"))
      (node (ref "PAD13") (pin "1") (pinfunction "P_1") (pintype "passive"))
      (node (ref "PAD14") (pin "1") (pinfunction "P_1") (pintype "passive"))
      (node (ref "POWER") (pin "3") (pinfunction "S_3") (pintype "passive"))
      (node (ref "PR3") (pin "E") (pinfunction "E_E") (pintype "passive"))
      (node (ref "PR3.") (pin "E") (pinfunction "E_E") (pintype "passive"))
      (node (ref "R29") (pin "2") (pinfunction "2_2") (pintype "passive"))
      (node (ref "R29.") (pin "2") (pinfunction "2_2") (pintype "passive"))
    )
    (net (code "3") (name "/BIAS") (class "Default")
      (node (ref "R16") (pin "1") (pinfunction "1_1") (pintype "passive"))
      (node (ref "R35") (pin "1") (pinfunction "1_1") (pintype "passive"))
      (node (ref "R36") (pin "2") (pinfunction "2_2") (pintype "passive"))
    )
    (net (code "4") (name "/BIAS2") (class "Default")
      (node (ref "R16.") (pin "1") (pinfunction "1_1") (pintype "passive"))
      (node (ref "R35.") (pin "1") (pinfunction "1_1") (pintype "passive"))
      (node (ref "R36.") (pin "2") (pinfunction "2_2") (pintype "passive"))
    )
    (net (code "5") (name "/EXCITATION_IN") (class "Default")
      (node (ref "CE4") (pin "+") (pinfunction "+_+") (pintype "passive"))
      (node (ref "P9.") (pin "1") (pinfunction "1_1") (pintype "passive"))
      (node (ref "PAD3") (pin "1") (pinfunction "P_1") (pintype "passive"))
      (node (ref "PAD4") (pin "1") (pinfunction "P_1") (pintype "passive"))
    )
    (net (code "6") (name "/OUT1") (class "Default")
      (node (ref "J1") (pin "3") (pinfunction "3_3") (pintype "passive"))
      (node (ref "J2") (pin "3") (pinfunction "3_3") (pintype "passive"))
      (node (ref "PAD1") (pin "1") (pinfunction "P_1") (pintype "passive"))
      (node (ref "PAD2") (pin "1") (pinfunction "P_1") (pintype "passive"))
    )
    (net (code "7") (name "/OUT2") (class "Default")
      (node (ref "J1") (pin "1") (pinfunction "1_1") (pintype "passive"))
      (node (ref "J2") (pin "1") (pinfunction "1_1") (pintype "passive"))
      (node (ref "PAD17") (pin "1") (pinfunction "P_1") (pintype "passive"))
      (node (ref "PAD18") (pin "1") (pinfunction "P_1") (pintype "passive"))
    )
    (net (code "8") (name "/OUTPUT_AMP") (class "Default")
      (node (ref "J1") (pin "2") (pinfunction "2_2") (pintype "passive"))
      (node (ref "R30") (pin "2") (pinfunction "2_2") (pintype "passive"))
    )
    (net (code "9") (name "/OUTPUT_AMP_2") (class "Default")
      (node (ref "J2") (pin "2") (pinfunction "2_2") (pintype "passive"))
      (node (ref "R30.") (pin "2") (pinfunction "2_2") (pintype "passive"))
    )
    (net (code "10") (name "/SLEW_RATE_CTRL") (class "Default")
      (node (ref "D3") (pin "C") (pinfunction "C_C") (pintype "passive"))
      (node (ref "D3.") (pin "C") (pinfunction "C_C") (pintype "passive"))
      (node (ref "PAD11") (pin "1") (pinfunction "P_1") (pintype "passive"))
      (node (ref "PAD12") (pin "1") (pinfunction "P_1") (pintype "passive"))
    )
    (net (code "11") (name "/SPEECH_IN") (class "Default")
      (node (ref "CE1") (pin "+") (pinfunction "+_+") (pintype "passive"))
      (node (ref "P1.") (pin "2") (pinfunction "2_2") (pintype "passive"))
      (node (ref "P1.") (pin "3") (pinfunction "2_3") (pintype "passive"))
      (node (ref "PAD5") (pin "1") (pinfunction "P_1") (pintype "passive"))
      (node (ref "PAD6") (pin "1") (pinfunction "P_1") (pintype "passive"))
    )
    (net (code "12") (name "/VU_DETECTOR") (class "Default")
      (node (ref "JP1") (pin "1") (pinfunction "1_1") (pintype "passive"))
      (node (ref "PAD7") (pin "1") (pinfunction "P_1") (pintype "passive"))
      (node (ref "R14") (pin "2") (pinfunction "2_2") (pintype "passive"))
    )
    (net (code "13") (name "/VU_DETECTOR_2") (class "Default")
      (node (ref "JP1") (pin "2") (pinfunction "2_2") (pintype "passive"))
      (node (ref "PAD8") (pin "1") (pinfunction "P_1") (pintype "passive"))
      (node (ref "R14.") (pin "2") (pinfunction "2_2") (pintype "passive"))
    )
    (net (code "14") (name "GND") (class "Default")
      (node (ref "C1") (pin "2") (pinfunction "2_2") (pintype "passive"))
      (node (ref "C10") (pin "2") (pinfunction "2_2") (pintype "passive"))
      (node (ref "C11") (pin "2") (pinfunction "2_2") (pintype "passive"))
      (node (ref "C13") (pin "2") (pinfunction "2_2") (pintype "passive"))
      (node (ref "C14") (pin "2") (pinfunction "2_2") (pintype "passive"))
      (node (ref "C15") (pin "2") (pinfunction "2_2") (pintype "passive"))
      (node (ref "C16") (pin "2") (pinfunction "2_2") (pintype "passive"))
      (node (ref "C17") (pin "1") (pinfunction "1_1") (pintype "passive"))
      (node (ref "C18") (pin "1") (pinfunction "1_1") (pintype "passive"))
      (node (ref "C19") (pin "1") (pinfunction "1_1") (pintype "passive"))
      (node (ref "C2") (pin "2") (pinfunction "2_2") (pintype "passive"))
      (node (ref "C20") (pin "1") (pinfunction "1_1") (pintype "passive"))
      (node (ref "C21") (pin "1") (pinfunction "1_1") (pintype "passive"))
      (node (ref "C22") (pin "1") (pinfunction "1_1") (pintype "passive"))
      (node (ref "C23") (pin "1") (pinfunction "1_1") (pintype "passive"))
      (node (ref "C24") (pin "1") (pinfunction "1_1") (pintype "passive"))
      (node (ref "C25") (pin "1") (pinfunction "1_1") (pintype "passive"))
      (node (ref "C26") (pin "1") (pinfunction "1_1") (pintype "passive"))
      (node (ref "C27") (pin "1") (pinfunction "1_1") (pintype "passive"))
      (node (ref "C28") (pin "1") (pinfunction "1_1") (pintype "passive"))
      (node (ref "C3") (pin "2") (pinfunction "2_2") (pintype "passive"))
      (node (ref "C4") (pin "2") (pinfunction "2_2") (pintype "passive"))
      (node (ref "C6") (pin "1") (pinfunction "1_1") (pintype "passive"))
      (node (ref "C6.") (pin "1") (pinfunction "1_1") (pintype "passive"))
      (node (ref "C7") (pin "2") (pinfunction "2_2") (pintype "passive"))
      (node (ref "C7.") (pin "2") (pinfunction "2_2") (pintype "passive"))
      (node (ref "C8") (pin "2") (pinfunction "2_2") (pintype "passive"))
      (node (ref "C9") (pin "2") (pinfunction "2_2") (pintype "passive"))
      (node (ref "IC2") (pin "5") (pinfunction "+IN_5") (pintype "input"))
      (node (ref "IC2.") (pin "5") (pinfunction "+IN_5") (pintype "input"))
      (node (ref "P12") (pin "1") (pinfunction "1_1") (pintype "passive"))
      (node (ref "P12.") (pin "1") (pinfunction "1_1") (pintype "passive"))
      (node (ref "P16") (pin "1") (pinfunction "1_1") (pintype "passive"))
      (node (ref "P16.") (pin "1") (pinfunction "1_1") (pintype "passive"))
      (node (ref "P4") (pin "1") (pinfunction "1_1") (pintype "passive"))
      (node (ref "P4.") (pin "1") (pinfunction "1_1") (pintype "passive"))
      (node (ref "P8") (pin "1") (pinfunction "1_1") (pintype "passive"))
      (node (ref "P8.") (pin "1") (pinfunction "1_1") (pintype "passive"))
      (node (ref "PAD15") (pin "1") (pinfunction "P_1") (pintype "passive"))
      (node (ref "PAD16") (pin "1") (pinfunction "P_1") (pintype "passive"))
      (node (ref "POWER") (pin "2") (pinfunction "S_2") (pintype "passive"))
      (node (ref "PR1") (pin "E") (pinfunction "E_E") (pintype "passive"))
      (node (ref "PR1") (pin "S") (pinfunction "S_S") (pintype "passive"))
      (node (ref "PR1") (pin "S0") (pinfunction "S_S0") (pintype "passive"))
      (node (ref "PR1.") (pin "E") (pinfunction "E_E") (pintype "passive"))
      (node (ref "PR1.") (pin "S") (pinfunction "S_S") (pintype "passive"))
      (node (ref "PR1.") (pin "S0") (pinfunction "S_S0") (pintype "passive"))
      (node (ref "PR4") (pin "S") (pinfunction "S_S") (pintype "passive"))
      (node (ref "PR4") (pin "S0") (pinfunction "S_S0") (pintype "passive"))
      (node (ref "PR4.") (pin "S") (pinfunction "S_S") (pintype "passive"))
      (node (ref "PR4.") (pin "S0") (pinfunction "S_S0") (pintype "passive"))
      (node (ref "PR5") (pin "E") (pinfunction "E_E") (pintype "passive"))
      (node (ref "PR5") (pin "S") (pinfunction "S_S") (pintype "passive"))
      (node (ref "PR5") (pin "S0") (pinfunction "S_S0") (pintype "passive"))
      (node (ref "PR5.") (pin "E") (pinfunction "E_E") (pintype "passive"))
      (node (ref "PR5.") (pin "S") (pinfunction "S_S") (pintype "passive"))
      (node (ref "PR5.") (pin "S0") (pinfunction "S_S0") (pintype "passive"))
      (node (ref "Q2") (pin "B") (pinfunction "B_B") (pintype "passive"))
      (node (ref "Q2.") (pin "B") (pinfunction "B_B") (pintype "passive"))
      (node (ref "R18") (pin "2") (pinfunction "2_2") (pintype "passive"))
      (node (ref "R18.") (pin "2") (pinfunction "2_2") (pintype "passive"))
      (node (ref "R36") (pin "1") (pinfunction "1_1") (pintype "passive"))
      (node (ref "R36.") (pin "1") (pinfunction "1_1") (pintype "passive"))
      (node (ref "RE1") (pin "1") (pinfunction "1_1") (pintype "passive"))
      (node (ref "RE2") (pin "1") (pinfunction "1_1") (pintype "passive"))
      (node (ref "RE2.") (pin "1") (pinfunction "1_1") (pintype "passive"))
      (node (ref "RE4") (pin "1") (pinfunction "1_1") (pintype "passive"))
      (node (ref "RE4.") (pin "1") (pinfunction "1_1") (pintype "passive"))
      (node (ref "RE6") (pin "1") (pinfunction "1_1") (pintype "passive"))
      (node (ref "RE7") (pin "1") (pinfunction "1_1") (pintype "passive"))
      (node (ref "RE7.") (pin "1") (pinfunction "1_1") (pintype "passive"))
      (node (ref "RE9") (pin "1") (pinfunction "1_1") (pintype "passive"))
      (node (ref "RE9.") (pin "1") (pinfunction "1_1") (pintype "passive"))
      (node (ref "RV1") (pin "1A") (pinfunction "1A_1A") (pintype "passive"))
      (node (ref "RV1.") (pin "1A") (pinfunction "1A_1A") (pintype "passive"))
    )
    (net (code "15") (name "Net-(C5-Pad2)") (class "Default")
      (node (ref "C5") (pin "2") (pinfunction "2_2") (pintype "passive"))
      (node (ref "R12") (pin "2") (pinfunction "2_2") (pintype "passive"))
      (node (ref "R13") (pin "1") (pinfunction "1_1") (pintype "passive"))
    )
    (net (code "16") (name "Net-(C5.-Pad2)") (class "Default")
      (node (ref "C5.") (pin "2") (pinfunction "2_2") (pintype "passive"))
      (node (ref "R12.") (pin "2") (pinfunction "2_2") (pintype "passive"))
      (node (ref "R13.") (pin "1") (pinfunction "1_1") (pintype "passive"))
    )
    (net (code "17") (name "Net-(C12-Pad1)") (class "Default")
      (node (ref "C12") (pin "1") (pinfunction "1_1") (pintype "passive"))
      (node (ref "R30") (pin "1") (pinfunction "1_1") (pintype "passive"))
    )
    (net (code "18") (name "Net-(C12.-Pad1)") (class "Default")
      (node (ref "C12.") (pin "1") (pinfunction "1_1") (pintype "passive"))
      (node (ref "R30.") (pin "1") (pinfunction "1_1") (pintype "passive"))
    )
    (net (code "19") (name "Net-(CE1-Pad-)") (class "Default")
      (node (ref "CE1") (pin "-") (pinfunction "-_-") (pintype "passive"))
      (node (ref "P1") (pin "2") (pinfunction "2_2") (pintype "passive"))
      (node (ref "RE1") (pin "2") (pinfunction "2_2") (pintype "passive"))
    )
    (net (code "20") (name "Net-(CE2-Pad1)") (class "Default")
      (node (ref "CE2") (pin "1") (pinfunction "1_1") (pintype "passive"))
      (node (ref "P1") (pin "1") (pinfunction "1_1") (pintype "passive"))
      (node (ref "P2") (pin "1") (pinfunction "1_1") (pintype "passive"))
      (node (ref "P3") (pin "1") (pinfunction "1_1") (pintype "passive"))
      (node (ref "PR1") (pin "A") (pinfunction "A_A") (pintype "passive"))
    )
    (net (code "21") (name "Net-(CE2.-Pad1)") (class "Default")
      (node (ref "CE2.") (pin "1") (pinfunction "1_1") (pintype "passive"))
      (node (ref "P1.") (pin "1") (pinfunction "1_1") (pintype "passive"))
      (node (ref "P2.") (pin "2") (pinfunction "2_2") (pintype "passive"))
      (node (ref "P2.") (pin "3") (pinfunction "2_3") (pintype "passive"))
      (node (ref "P3.") (pin "1") (pinfunction "1_1") (pintype "passive"))
      (node (ref "PR1.") (pin "A") (pinfunction "A_A") (pintype "passive"))
    )
    (net (code "22") (name "Net-(CE3-Pad1)") (class "Default")
      (node (ref "CE3") (pin "1") (pinfunction "1_1") (pintype "passive"))
      (node (ref "P5") (pin "2") (pinfunction "2_2") (pintype "passive"))
      (node (ref "P6") (pin "1") (pinfunction "1_1") (pintype "passive"))
      (node (ref "P7") (pin "1") (pinfunction "1_1") (pintype "passive"))
      (node (ref "RE4") (pin "2") (pinfunction "2_2") (pintype "passive"))
    )
    (net (code "23") (name "Net-(CE3.-Pad1)") (class "Default")
      (node (ref "CE3.") (pin "1") (pinfunction "1_1") (pintype "passive"))
      (node (ref "P5.") (pin "2") (pinfunction "2_2") (pintype "passive"))
      (node (ref "P5.") (pin "3") (pinfunction "2_3") (pintype "passive"))
      (node (ref "P6.") (pin "1") (pinfunction "1_1") (pintype "passive"))
      (node (ref "P7.") (pin "1") (pinfunction "1_1") (pintype "passive"))
      (node (ref "RE4.") (pin "2") (pinfunction "2_2") (pintype "passive"))
    )
    (net (code "24") (name "Net-(CE4-Pad-)") (class "Default")
      (node (ref "CE4") (pin "-") (pinfunction "-_-") (pintype "passive"))
      (node (ref "P9") (pin "1") (pinfunction "1_1") (pintype "passive"))
    )
    (net (code "25") (name "Net-(CE5-Pad2)") (class "Default")
      (node (ref "CE5") (pin "2") (pinfunction "2_2") (pintype "passive"))
      (node (ref "P10") (pin "2") (pinfunction "2_2") (pintype "passive"))
      (node (ref "P11") (pin "1") (pinfunction "1_1") (pintype "passive"))
      (node (ref "P9") (pin "2") (pinfunction "2_2") (pintype "passive"))
      (node (ref "PR5") (pin "A") (pinfunction "A_A") (pintype "passive"))
    )
    (net (code "26") (name "Net-(CE5.-Pad2)") (class "Default")
      (node (ref "CE5.") (pin "2") (pinfunction "2_2") (pintype "passive"))
      (node (ref "P10.") (pin "1") (pinfunction "1_1") (pintype "passive"))
      (node (ref "P11.") (pin "1") (pinfunction "1_1") (pintype "passive"))
      (node (ref "P9.") (pin "2") (pinfunction "2_2") (pintype "passive"))
      (node (ref "P9.") (pin "3") (pinfunction "2_3") (pintype "passive"))
      (node (ref "PR5.") (pin "A") (pinfunction "A_A") (pintype "passive"))
    )
    (net (code "27") (name "Net-(CE6-Pad2)") (class "Default")
      (node (ref "CE6") (pin "2") (pinfunction "2_2") (pintype "passive"))
      (node (ref "P13") (pin "2") (pinfunction "2_2") (pintype "passive"))
      (node (ref "P14") (pin "2") (pinfunction "2_2") (pintype "passive"))
      (node (ref "P15") (pin "1") (pinfunction "1_1") (pintype "passive"))
      (node (ref "RE9") (pin "2") (pinfunction "2_2") (pintype "passive"))
    )
    (net (code "28") (name "Net-(CE6.-Pad2)") (class "Default")
      (node (ref "CE6.") (pin "2") (pinfunction "2_2") (pintype "passive"))
      (node (ref "P13.") (pin "1") (pinfunction "1_1") (pintype "passive"))
      (node (ref "P14.") (pin "2") (pinfunction "2_2") (pintype "passive"))
      (node (ref "P14.") (pin "3") (pinfunction "2_3") (pintype "passive"))
    )
    (net (code "29") (name "Net-(D2-PadA)") (class "Default")
      (node (ref "D2") (pin "A") (pinfunction "A_A") (pintype "passive"))
      (node (ref "R10") (pin "1") (pinfunction "1_1") (pintype "passive"))
      (node (ref "R9") (pin "2") (pinfunction "2_2") (pintype "passive"))
    )
    (net (code "30") (name "Net-(D2.-PadA)") (class "Default")
      (node (ref "D2.") (pin "A") (pinfunction "A_A") (pintype "passive"))
      (node (ref "R10.") (pin "1") (pinfunction "1_1") (pintype "passive"))
      (node (ref "R9.") (pin "2") (pinfunction "2_2") (pintype "passive"))
    )
    (net (code "31") (name "Net-(D3-PadA)") (class "Default")
      (node (ref "D3") (pin "A") (pinfunction "A_A") (pintype "passive"))
      (node (ref "Q1") (pin "G") (pinfunction "G_G") (pintype "passive"))
      (node (ref "R17") (pin "2") (pinfunction "2_2") (pintype "passive"))
    )
    (net (code "32") (name "Net-(D3.-PadA)") (class "Default")
      (node (ref "D3.") (pin "A") (pinfunction "A_A") (pintype "passive"))
      (node (ref "Q1.") (pin "G") (pinfunction "G_G") (pintype "passive"))
      (node (ref "R17.") (pin "2") (pinfunction "2_2") (pintype "passive"))
    )
    (net (code "33") (name "Net-(IC1.A-+IN)") (class "Default")
      (node (ref "IC1.") (pin "3") (pinfunction "+IN_3") (pintype "input"))
      (node (ref "P3.") (pin "2") (pinfunction "2_2") (pintype "passive"))
      (node (ref "P4.") (pin "2") (pinfunction "2_2") (pintype "passive"))
    )
    (net (code "34") (name "Net-(IC1.A--IN)") (class "Default")
      (node (ref "IC1.") (pin "2") (pinfunction "-IN_2") (pintype "input"))
      (node (ref "P2.") (pin "1") (pinfunction "1_1") (pintype "passive"))
      (node (ref "RE2.") (pin "2") (pinfunction "2_2") (pintype "passive"))
      (node (ref "RE3.") (pin "1") (pinfunction "1_1") (pintype "passive"))
    )
    (net (code "35") (name "Net-(IC1.A-OUT)") (class "Default")
      (node (ref "CE2.") (pin "2") (pinfunction "2_2") (pintype "passive"))
      (node (ref "IC1.") (pin "1") (pinfunction "OUT_1") (pintype "output"))
      (node (ref "P5.") (pin "1") (pinfunction "1_1") (pintype "passive"))
      (node (ref "RE3.") (pin "2") (pinfunction "2_2") (pintype "passive"))
    )
    (net (code "36") (name "Net-(IC1.B-+IN)") (class "Default")
      (node (ref "IC1.") (pin "5") (pinfunction "+IN_5") (pintype "input"))
      (node (ref "P7.") (pin "2") (pinfunction "2_2") (pintype "passive"))
      (node (ref "P8.") (pin "2") (pinfunction "2_2") (pintype "passive"))
    )
    (net (code "37") (name "Net-(IC1.B--IN)") (class "Default")
      (node (ref "IC1.") (pin "6") (pinfunction "-IN_6") (pintype "input"))
      (node (ref "P6.") (pin "2") (pinfunction "2_2") (pintype "passive"))
      (node (ref "P6.") (pin "3") (pinfunction "2_3") (pintype "passive"))
      (node (ref "RE5.") (pin "2") (pinfunction "2_2") (pintype "passive"))
    )
    (net (code "38") (name "Net-(IC1.B-OUT)") (class "Default")
      (node (ref "CE3.") (pin "2") (pinfunction "2_2") (pintype "passive"))
      (node (ref "IC1.") (pin "7") (pinfunction "OUT_7") (pintype "output"))
      (node (ref "R7.") (pin "1") (pinfunction "1_1") (pintype "passive"))
      (node (ref "RE5.") (pin "1") (pinfunction "1_1") (pintype "passive"))
    )
    (net (code "39") (name "Net-(IC1A-+IN)") (class "Default")
      (node (ref "IC1") (pin "3") (pinfunction "+IN_3") (pintype "input"))
      (node (ref "P3") (pin "2") (pinfunction "2_2") (pintype "passive"))
      (node (ref "P4") (pin "2") (pinfunction "2_2") (pintype "passive"))
    )
    (net (code "40") (name "Net-(IC1A--IN)") (class "Default")
      (node (ref "IC1") (pin "2") (pinfunction "-IN_2") (pintype "input"))
      (node (ref "P2") (pin "2") (pinfunction "2_2") (pintype "passive"))
      (node (ref "RE2") (pin "2") (pinfunction "2_2") (pintype "passive"))
      (node (ref "RE3") (pin "1") (pinfunction "1_1") (pintype "passive"))
    )
    (net (code "41") (name "Net-(IC1A-OUT)") (class "Default")
      (node (ref "CE2") (pin "2") (pinfunction "2_2") (pintype "passive"))
      (node (ref "IC1") (pin "1") (pinfunction "OUT_1") (pintype "output"))
      (node (ref "P5") (pin "1") (pinfunction "1_1") (pintype "passive"))
      (node (ref "RE3") (pin "2") (pinfunction "2_2") (pintype "passive"))
    )
    (net (code "42") (name "Net-(IC1B-+IN)") (class "Default")
      (node (ref "IC1") (pin "5") (pinfunction "+IN_5") (pintype "input"))
      (node (ref "P7") (pin "2") (pinfunction "2_2") (pintype "passive"))
      (node (ref "P8") (pin "2") (pinfunction "2_2") (pintype "passive"))
      (node (ref "P8") (pin "3") (pinfunction "2_3") (pintype "passive"))
    )
    (net (code "43") (name "Net-(IC1B--IN)") (class "Default")
      (node (ref "IC1") (pin "6") (pinfunction "-IN_6") (pintype "input"))
      (node (ref "P6") (pin "2") (pinfunction "2_2") (pintype "passive"))
      (node (ref "RE5") (pin "2") (pinfunction "2_2") (pintype "passive"))
    )
    (net (code "44") (name "Net-(IC1B-OUT)") (class "Default")
      (node (ref "CE3") (pin "2") (pinfunction "2_2") (pintype "passive"))
      (node (ref "IC1") (pin "7") (pinfunction "OUT_7") (pintype "output"))
      (node (ref "R7") (pin "1") (pinfunction "1_1") (pintype "passive"))
      (node (ref "RE5") (pin "1") (pinfunction "1_1") (pintype "passive"))
    )
    (net (code "45") (name "Net-(IC2.A-+IN)") (class "Default")
      (node (ref "D1.") (pin "C") (pinfunction "C_C") (pintype "passive"))
      (node (ref "IC2.") (pin "3") (pinfunction "+IN_3") (pintype "input"))
      (node (ref "R8.") (pin "2") (pinfunction "2_2") (pintype "passive"))
    )
    (net (code "46") (name "Net-(IC2.A--IN)") (class "Default")
      (node (ref "IC2.") (pin "2") (pinfunction "-IN_2") (pintype "input"))
      (node (ref "R10.") (pin "2") (pinfunction "2_2") (pintype "passive"))
      (node (ref "R11.") (pin "1") (pinfunction "1_1") (pintype "passive"))
    )
    (net (code "47") (name "Net-(IC2.A-OUT)") (class "Default")
      (node (ref "IC2.") (pin "1") (pinfunction "OUT_1") (pintype "output"))
      (node (ref "R11.") (pin "2") (pinfunction "2_2") (pintype "passive"))
      (node (ref "R12.") (pin "1") (pinfunction "1_1") (pintype "passive"))
    )
    (net (code "48") (name "Net-(IC2.B--IN)") (class "Default")
      (node (ref "IC2.") (pin "6") (pinfunction "-IN_6") (pintype "input"))
      (node (ref "R7.") (pin "2") (pinfunction "2_2") (pintype "passive"))
      (node (ref "R8.") (pin "1") (pinfunction "1_1") (pintype "passive"))
      (node (ref "R9.") (pin "1") (pinfunction "1_1") (pintype "passive"))
    )
    (net (code "49") (name "Net-(IC2.B-OUT)") (class "Default")
      (node (ref "D1.") (pin "A") (pinfunction "A_A") (pintype "passive"))
      (node (ref "D2.") (pin "C") (pinfunction "C_C") (pintype "passive"))
      (node (ref "IC2.") (pin "7") (pinfunction "OUT_7") (pintype "output"))
    )
    (net (code "50") (name "Net-(IC2A-+IN)") (class "Default")
      (node (ref "D1") (pin "C") (pinfunction "C_C") (pintype "passive"))
      (node (ref "IC2") (pin "3") (pinfunction "+IN_3") (pintype "input"))
      (node (ref "R8") (pin "2") (pinfunction "2_2") (pintype "passive"))
    )
    (net (code "51") (name "Net-(IC2A--IN)") (class "Default")
      (node (ref "IC2") (pin "2") (pinfunction "-IN_2") (pintype "input"))
      (node (ref "R10") (pin "2") (pinfunction "2_2") (pintype "passive"))
      (node (ref "R11") (pin "1") (pinfunction "1_1") (pintype "passive"))
    )
    (net (code "52") (name "Net-(IC2A-OUT)") (class "Default")
      (node (ref "IC2") (pin "1") (pinfunction "OUT_1") (pintype "output"))
      (node (ref "R11") (pin "2") (pinfunction "2_2") (pintype "passive"))
      (node (ref "R12") (pin "1") (pinfunction "1_1") (pintype "passive"))
    )
    (net (code "53") (name "Net-(IC2B--IN)") (class "Default")
      (node (ref "IC2") (pin "6") (pinfunction "-IN_6") (pintype "input"))
      (node (ref "R7") (pin "2") (pinfunction "2_2") (pintype "passive"))
      (node (ref "R8") (pin "1") (pinfunction "1_1") (pintype "passive"))
      (node (ref "R9") (pin "1") (pinfunction "1_1") (pintype "passive"))
    )
    (net (code "54") (name "Net-(IC2B-OUT)") (class "Default")
      (node (ref "D1") (pin "A") (pinfunction "A_A") (pintype "passive"))
      (node (ref "D2") (pin "C") (pinfunction "C_C") (pintype "passive"))
      (node (ref "IC2") (pin "7") (pinfunction "OUT_7") (pintype "output"))
    )
    (net (code "55") (name "Net-(IC3-+IN)") (class "Default")
      (node (ref "C6") (pin "2") (pinfunction "2_2") (pintype "passive"))
      (node (ref "IC3") (pin "3") (pinfunction "+IN_3") (pintype "input"))
      (node (ref "R13") (pin "2") (pinfunction "2_2") (pintype "passive"))
    )
    (net (code "56") (name "Net-(IC3--IN)") (class "Default")
      (node (ref "C5") (pin "1") (pinfunction "1_1") (pintype "passive"))
      (node (ref "IC3") (pin "2") (pinfunction "-IN_2") (pintype "input"))
      (node (ref "IC3") (pin "6") (pinfunction "OUT_6") (pintype "output"))
      (node (ref "R14") (pin "1") (pinfunction "1_1") (pintype "passive"))
      (node (ref "R15") (pin "2") (pinfunction "2_2") (pintype "passive"))
    )
    (net (code "57") (name "Net-(IC3.-+IN)") (class "Default")
      (node (ref "C6.") (pin "2") (pinfunction "2_2") (pintype "passive"))
      (node (ref "IC3.") (pin "3") (pinfunction "+IN_3") (pintype "input"))
      (node (ref "R13.") (pin "2") (pinfunction "2_2") (pintype "passive"))
    )
    (net (code "58") (name "Net-(IC3.--IN)") (class "Default")
      (node (ref "C5.") (pin "1") (pinfunction "1_1") (pintype "passive"))
      (node (ref "IC3.") (pin "2") (pinfunction "-IN_2") (pintype "input"))
      (node (ref "IC3.") (pin "6") (pinfunction "OUT_6") (pintype "output"))
      (node (ref "R14.") (pin "1") (pinfunction "1_1") (pintype "passive"))
      (node (ref "R15.") (pin "2") (pinfunction "2_2") (pintype "passive"))
    )
    (net (code "59") (name "Net-(IC4-+IN)") (class "Default")
      (node (ref "C7") (pin "1") (pinfunction "1_1") (pintype "passive"))
      (node (ref "IC4") (pin "3") (pinfunction "+IN_3") (pintype "input"))
      (node (ref "Q1") (pin "S") (pinfunction "S_S") (pintype "passive"))
    )
    (net (code "60") (name "Net-(IC4--IN)") (class "Default")
      (node (ref "IC4") (pin "2") (pinfunction "-IN_2") (pintype "input"))
      (node (ref "IC4") (pin "6") (pinfunction "OUT_6") (pintype "output"))
      (node (ref "IC5") (pin "3") (pinfunction "+IN_3") (pintype "input"))
      (node (ref "R17") (pin "1") (pinfunction "1_1") (pintype "passive"))
    )
    (net (code "61") (name "Net-(IC4.-+IN)") (class "Default")
      (node (ref "C7.") (pin "1") (pinfunction "1_1") (pintype "passive"))
      (node (ref "IC4.") (pin "3") (pinfunction "+IN_3") (pintype "input"))
      (node (ref "Q1.") (pin "S") (pinfunction "S_S") (pintype "passive"))
    )
    (net (code "62") (name "Net-(IC4.--IN)") (class "Default")
      (node (ref "IC4.") (pin "2") (pinfunction "-IN_2") (pintype "input"))
      (node (ref "IC4.") (pin "6") (pinfunction "OUT_6") (pintype "output"))
      (node (ref "IC5") (pin "5") (pinfunction "+IN_5") (pintype "input"))
      (node (ref "R17.") (pin "1") (pinfunction "1_1") (pintype "passive"))
    )
    (net (code "63") (name "Net-(IC5A--IN)") (class "Default")
      (node (ref "D4") (pin "C") (pinfunction "C_C") (pintype "passive"))
      (node (ref "IC5") (pin "2") (pinfunction "-IN_2") (pintype "input"))
      (node (ref "R18") (pin "1") (pinfunction "1_1") (pintype "passive"))
    )
    (net (code "64") (name "Net-(IC5A-OUT)") (class "Default")
      (node (ref "D4") (pin "A") (pinfunction "A_A") (pintype "passive"))
      (node (ref "IC5") (pin "1") (pinfunction "OUT_1") (pintype "output"))
      (node (ref "PR2") (pin "E") (pinfunction "E_E") (pintype "passive"))
    )
    (net (code "65") (name "Net-(IC5B--IN)") (class "Default")
      (node (ref "D4.") (pin "C") (pinfunction "C_C") (pintype "passive"))
      (node (ref "IC5") (pin "6") (pinfunction "-IN_6") (pintype "input"))
      (node (ref "R18.") (pin "1") (pinfunction "1_1") (pintype "passive"))
    )
    (net (code "66") (name "Net-(IC5B-OUT)") (class "Default")
      (node (ref "D4.") (pin "A") (pinfunction "A_A") (pintype "passive"))
      (node (ref "IC5") (pin "7") (pinfunction "OUT_7") (pintype "output"))
      (node (ref "PR2.") (pin "E") (pinfunction "E_E") (pintype "passive"))
    )
    (net (code "67") (name "Net-(IC6A-+IN)") (class "Default")
      (node (ref "IC6") (pin "3") (pinfunction "+IN_3") (pintype "input"))
      (node (ref "R32") (pin "2") (pinfunction "2_2") (pintype "passive"))
    )
    (net (code "68") (name "Net-(IC6A--IN)") (class "Default")
      (node (ref "IC6") (pin "4") (pinfunction "-IN_4") (pintype "input"))
      (node (ref "R27") (pin "2") (pinfunction "2_2") (pintype "passive"))
      (node (ref "R31") (pin "1") (pinfunction "1_1") (pintype "passive"))
    )
    (net (code "69") (name "Net-(IC6A-AMP{slash}BIAS)") (class "Default")
      (node (ref "IC6") (pin "1") (pinfunction "AMP/BIAS_1") (pintype "passive"))
      (node (ref "R20") (pin "1") (pinfunction "1_1") (pintype "passive"))
    )
    (net (code "70") (name "Net-(IC6A-BUFF{slash}IN)") (class "Default")
      (node (ref "IC6") (pin "7") (pinfunction "BUFF/IN_7") (pintype "input"))
      (node (ref "RV1") (pin "1S") (pinfunction "1S_1S") (pintype "passive"))
    )
    (net (code "71") (name "Net-(IC6A-BUFF{slash}OUT)") (class "Default")
      (node (ref "C12") (pin "2") (pinfunction "2_2") (pintype "passive"))
      (node (ref "IC6") (pin "8") (pinfunction "BUFF/OUT_8") (pintype "output"))
      (node (ref "R29") (pin "1") (pinfunction "1_1") (pintype "passive"))
    )
    (net (code "72") (name "Net-(IC6A-DIODE{slash}BIAS)") (class "Default")
      (node (ref "IC6") (pin "2") (pinfunction "DIODE/BIAS_2") (pintype "passive"))
      (node (ref "R28") (pin "1") (pinfunction "1_1") (pintype "passive"))
    )
    (net (code "73") (name "Net-(IC6A-OUT)") (class "Default")
      (node (ref "IC6") (pin "5") (pinfunction "OUT_5") (pintype "output"))
      (node (ref "RV1") (pin "1E") (pinfunction "1E_1E") (pintype "passive"))
    )
    (net (code "74") (name "Net-(IC6B-+IN)") (class "Default")
      (node (ref "IC6") (pin "14") (pinfunction "+IN_14") (pintype "input"))
      (node (ref "R32.") (pin "2") (pinfunction "2_2") (pintype "passive"))
    )
    (net (code "75") (name "Net-(IC6B--IN)") (class "Default")
      (node (ref "IC6") (pin "13") (pinfunction "-IN_13") (pintype "input"))
      (node (ref "R27.") (pin "2") (pinfunction "2_2") (pintype "passive"))
      (node (ref "R31.") (pin "1") (pinfunction "1_1") (pintype "passive"))
    )
    (net (code "76") (name "Net-(IC6B-AMP{slash}BIAS)") (class "Default")
      (node (ref "IC6") (pin "16") (pinfunction "AMP/BIAS_16") (pintype "passive"))
      (node (ref "R20.") (pin "1") (pinfunction "1_1") (pintype "passive"))
    )
    (net (code "77") (name "Net-(IC6B-BUFF{slash}IN)") (class "Default")
      (node (ref "IC6") (pin "10") (pinfunction "BUFF/IN_10") (pintype "input"))
      (node (ref "RV1.") (pin "1S") (pinfunction "1S_1S") (pintype "passive"))
    )
    (net (code "78") (name "Net-(IC6B-BUFF{slash}OUT)") (class "Default")
      (node (ref "C12.") (pin "2") (pinfunction "2_2") (pintype "passive"))
      (node (ref "IC6") (pin "9") (pinfunction "BUFF/OUT_9") (pintype "output"))
      (node (ref "R29.") (pin "1") (pinfunction "1_1") (pintype "passive"))
    )
    (net (code "79") (name "Net-(IC6B-DIODE{slash}BIAS)") (class "Default")
      (node (ref "IC6") (pin "15") (pinfunction "DIODE/BIAS_15") (pintype "passive"))
      (node (ref "R28.") (pin "1") (pinfunction "1_1") (pintype "passive"))
    )
    (net (code "80") (name "Net-(IC6B-OUT)") (class "Default")
      (node (ref "IC6") (pin "12") (pinfunction "OUT_12") (pintype "output"))
      (node (ref "RV1.") (pin "1E") (pinfunction "1E_1E") (pintype "passive"))
    )
    (net (code "81") (name "Net-(IC7.A-+IN)") (class "Default")
      (node (ref "IC7.") (pin "3") (pinfunction "+IN_3") (pintype "input"))
      (node (ref "P11.") (pin "2") (pinfunction "2_2") (pintype "passive"))
      (node (ref "P12.") (pin "2") (pinfunction "2_2") (pintype "passive"))
    )
    (net (code "82") (name "Net-(IC7.A--IN)") (class "Default")
      (node (ref "IC7.") (pin "2") (pinfunction "-IN_2") (pintype "input"))
      (node (ref "P10.") (pin "2") (pinfunction "2_2") (pintype "passive"))
      (node (ref "P10.") (pin "3") (pinfunction "2_3") (pintype "passive"))
      (node (ref "RE7.") (pin "2") (pinfunction "2_2") (pintype "passive"))
      (node (ref "RE8.") (pin "1") (pinfunction "1_1") (pintype "passive"))
    )
    (net (code "83") (name "Net-(IC7.A-OUT)") (class "Default")
      (node (ref "CE5.") (pin "1") (pinfunction "1_1") (pintype "passive"))
      (node (ref "IC7.") (pin "1") (pinfunction "OUT_1") (pintype "output"))
      (node (ref "P13.") (pin "2") (pinfunction "2_2") (pintype "passive"))
      (node (ref "P13.") (pin "3") (pinfunction "2_3") (pintype "passive"))
      (node (ref "RE8.") (pin "2") (pinfunction "2_2") (pintype "passive"))
    )
    (net (code "84") (name "Net-(IC7.B-+IN)") (class "Default")
      (node (ref "IC7.") (pin "5") (pinfunction "+IN_5") (pintype "input"))
      (node (ref "P15.") (pin "2") (pinfunction "2_2") (pintype "passive"))
      (node (ref "P16.") (pin "2") (pinfunction "2_2") (pintype "passive"))
    )
    (net (code "85") (name "Net-(IC7.B--IN)") (class "Default")
      (node (ref "IC7.") (pin "6") (pinfunction "-IN_6") (pintype "input"))
      (node (ref "P14.") (pin "1") (pinfunction "1_1") (pintype "passive"))
      (node (ref "RE10.") (pin "1") (pinfunction "1_1") (pintype "passive"))
    )
    (net (code "86") (name "Net-(IC7.B-OUT)") (class "Default")
      (node (ref "CE6.") (pin "1") (pinfunction "1_1") (pintype "passive"))
      (node (ref "IC7.") (pin "7") (pinfunction "OUT_7") (pintype "output"))
      (node (ref "R27.") (pin "1") (pinfunction "1_1") (pintype "passive"))
      (node (ref "RE10.") (pin "2") (pinfunction "2_2") (pintype "passive"))
    )
    (net (code "87") (name "Net-(IC7A-+IN)") (class "Default")
      (node (ref "IC7") (pin "3") (pinfunction "+IN_3") (pintype "input"))
      (node (ref "P11") (pin "2") (pinfunction "2_2") (pintype "passive"))
      (node (ref "P12") (pin "2") (pinfunction "2_2") (pintype "passive"))
      (node (ref "RE6") (pin "2") (pinfunction "2_2") (pintype "passive"))
    )
    (net (code "88") (name "Net-(IC7A--IN)") (class "Default")
      (node (ref "IC7") (pin "2") (pinfunction "-IN_2") (pintype "input"))
      (node (ref "P10") (pin "1") (pinfunction "1_1") (pintype "passive"))
      (node (ref "RE7") (pin "2") (pinfunction "2_2") (pintype "passive"))
      (node (ref "RE8") (pin "1") (pinfunction "1_1") (pintype "passive"))
    )
    (net (code "89") (name "Net-(IC7A-OUT)") (class "Default")
      (node (ref "CE5") (pin "1") (pinfunction "1_1") (pintype "passive"))
      (node (ref "IC7") (pin "1") (pinfunction "OUT_1") (pintype "output"))
      (node (ref "P13") (pin "1") (pinfunction "1_1") (pintype "passive"))
      (node (ref "RE8") (pin "2") (pinfunction "2_2") (pintype "passive"))
    )
    (net (code "90") (name "Net-(IC7B-+IN)") (class "Default")
      (node (ref "IC7") (pin "5") (pinfunction "+IN_5") (pintype "input"))
      (node (ref "P15") (pin "2") (pinfunction "2_2") (pintype "passive"))
      (node (ref "P16") (pin "2") (pinfunction "2_2") (pintype "passive"))
      (node (ref "P16") (pin "3") (pinfunction "2_3") (pintype "passive"))
    )
    (net (code "91") (name "Net-(IC7B--IN)") (class "Default")
      (node (ref "IC7") (pin "6") (pinfunction "-IN_6") (pintype "input"))
      (node (ref "P14") (pin "1") (pinfunction "1_1") (pintype "passive"))
      (node (ref "RE10") (pin "1") (pinfunction "1_1") (pintype "passive"))
    )
    (net (code "92") (name "Net-(IC7B-OUT)") (class "Default")
      (node (ref "CE6") (pin "1") (pinfunction "1_1") (pintype "passive"))
      (node (ref "IC7") (pin "7") (pinfunction "OUT_7") (pintype "output"))
      (node (ref "R27") (pin "1") (pinfunction "1_1") (pintype "passive"))
      (node (ref "RE10") (pin "2") (pinfunction "2_2") (pintype "passive"))
    )
    (net (code "93") (name "Net-(P15.-Pad1)") (class "Default")
      (node (ref "P15.") (pin "1") (pinfunction "1_1") (pintype "passive"))
      (node (ref "RE9.") (pin "2") (pinfunction "2_2") (pintype "passive"))
    )
    (net (code "94") (name "Net-(PR2-PadA)") (class "Default")
      (node (ref "PR2") (pin "A") (pinfunction "A_A") (pintype "passive"))
      (node (ref "PR2") (pin "S") (pinfunction "S_S") (pintype "passive"))
      (node (ref "PR2") (pin "S0") (pinfunction "S_S0") (pintype "passive"))
      (node (ref "Q2") (pin "E") (pinfunction "E_E") (pintype "passive"))
      (node (ref "R19") (pin "1") (pinfunction "1_1") (pintype "passive"))
    )
    (net (code "95") (name "Net-(PR2.-PadA)") (class "Default")
      (node (ref "PR2.") (pin "A") (pinfunction "A_A") (pintype "passive"))
      (node (ref "PR2.") (pin "S") (pinfunction "S_S") (pintype "passive"))
      (node (ref "PR2.") (pin "S0") (pinfunction "S_S0") (pintype "passive"))
      (node (ref "Q2.") (pin "E") (pinfunction "E_E") (pintype "passive"))
      (node (ref "R19.") (pin "1") (pinfunction "1_1") (pintype "passive"))
    )
    (net (code "96") (name "Net-(PR3-PadS)") (class "Default")
      (node (ref "PR3") (pin "S") (pinfunction "S_S") (pintype "passive"))
      (node (ref "PR3") (pin "S0") (pinfunction "S_S0") (pintype "passive"))
      (node (ref "R19") (pin "2") (pinfunction "2_2") (pintype "passive"))
    )
    (net (code "97") (name "Net-(PR3.-PadS)") (class "Default")
      (node (ref "PR3.") (pin "S") (pinfunction "S_S") (pintype "passive"))
      (node (ref "PR3.") (pin "S0") (pinfunction "S_S0") (pintype "passive"))
      (node (ref "R19.") (pin "2") (pinfunction "2_2") (pintype "passive"))
    )
    (net (code "98") (name "Net-(PR4-PadA)") (class "Default")
      (node (ref "PR4") (pin "A") (pinfunction "A_A") (pintype "passive"))
      (node (ref "R31") (pin "2") (pinfunction "2_2") (pintype "passive"))
    )
    (net (code "99") (name "Net-(PR4-PadE)") (class "Default")
      (node (ref "PR4") (pin "E") (pinfunction "E_E") (pintype "passive"))
      (node (ref "R32") (pin "1") (pinfunction "1_1") (pintype "passive"))
    )
    (net (code "100") (name "Net-(PR4.-PadA)") (class "Default")
      (node (ref "PR4.") (pin "A") (pinfunction "A_A") (pintype "passive"))
      (node (ref "R31.") (pin "2") (pinfunction "2_2") (pintype "passive"))
    )
    (net (code "101") (name "Net-(PR4.-PadE)") (class "Default")
      (node (ref "PR4.") (pin "E") (pinfunction "E_E") (pintype "passive"))
      (node (ref "R32.") (pin "1") (pinfunction "1_1") (pintype "passive"))
    )
    (net (code "102") (name "Net-(Q1-D-PadD2)") (class "Default")
      (node (ref "Q1") (pin "D") (pinfunction "D_D") (pintype "passive"))
      (node (ref "Q1") (pin "D2") (pinfunction "D_D2") (pintype "passive"))
      (node (ref "R15") (pin "1") (pinfunction "1_1") (pintype "passive"))
      (node (ref "R16") (pin "2") (pinfunction "2_2") (pintype "passive"))
    )
    (net (code "103") (name "Net-(Q1.-D-PadD2)") (class "Default")
      (node (ref "Q1.") (pin "D") (pinfunction "D_D") (pintype "passive"))
      (node (ref "Q1.") (pin "D2") (pinfunction "D_D2") (pintype "passive"))
      (node (ref "R15.") (pin "1") (pinfunction "1_1") (pintype "passive"))
      (node (ref "R16.") (pin "2") (pinfunction "2_2") (pintype "passive"))
    )
    (net (code "104") (name "Net-(Q2-PadC)") (class "Default")
      (node (ref "Q2") (pin "C") (pinfunction "C_C") (pintype "passive"))
      (node (ref "R20") (pin "2") (pinfunction "2_2") (pintype "passive"))
    )
    (net (code "105") (name "Net-(Q2.-PadC)") (class "Default")
      (node (ref "Q2.") (pin "C") (pinfunction "C_C") (pintype "passive"))
      (node (ref "R20.") (pin "2") (pinfunction "2_2") (pintype "passive"))
    )
    (net (code "106") (name "unconnected-(IC3-ON1-Pad1)") (class "Default")
      (node (ref "IC3") (pin "1") (pinfunction "ON1_1") (pintype "passive"))
    )
    (net (code "107") (name "unconnected-(IC3-ON2-Pad5)") (class "Default")
      (node (ref "IC3") (pin "5") (pinfunction "ON2_5") (pintype "passive"))
    )
    (net (code "108") (name "unconnected-(IC3-OPT-Pad8)") (class "Default")
      (node (ref "IC3") (pin "8") (pinfunction "OPT_8") (pintype "passive"))
    )
    (net (code "109") (name "unconnected-(IC3.-ON1-Pad1)") (class "Default")
      (node (ref "IC3.") (pin "1") (pinfunction "ON1_1") (pintype "passive"))
    )
    (net (code "110") (name "unconnected-(IC3.-ON2-Pad5)") (class "Default")
      (node (ref "IC3.") (pin "5") (pinfunction "ON2_5") (pintype "passive"))
    )
    (net (code "111") (name "unconnected-(IC3.-OPT-Pad8)") (class "Default")
      (node (ref "IC3.") (pin "8") (pinfunction "OPT_8") (pintype "passive"))
    )
    (net (code "112") (name "unconnected-(IC4-ON1-Pad1)") (class "Default")
      (node (ref "IC4") (pin "1") (pinfunction "ON1_1") (pintype "passive"))
    )
    (net (code "113") (name "unconnected-(IC4-ON2-Pad5)") (class "Default")
      (node (ref "IC4") (pin "5") (pinfunction "ON2_5") (pintype "passive"))
    )
    (net (code "114") (name "unconnected-(IC4-OPT-Pad8)") (class "Default")
      (node (ref "IC4") (pin "8") (pinfunction "OPT_8") (pintype "passive"))
    )
    (net (code "115") (name "unconnected-(IC4.-ON1-Pad1)") (class "Default")
      (node (ref "IC4.") (pin "1") (pinfunction "ON1_1") (pintype "passive"))
    )
    (net (code "116") (name "unconnected-(IC4.-ON2-Pad5)") (class "Default")
      (node (ref "IC4.") (pin "5") (pinfunction "ON2_5") (pintype "passive"))
    )
    (net (code "117") (name "unconnected-(IC4.-OPT-Pad8)") (class "Default")
      (node (ref "IC4.") (pin "8") (pinfunction "OPT_8") (pintype "passive"))
    )
  )
)
